# socket-a-1.net
KiCad netlist of a schematic drawn in EAGLE
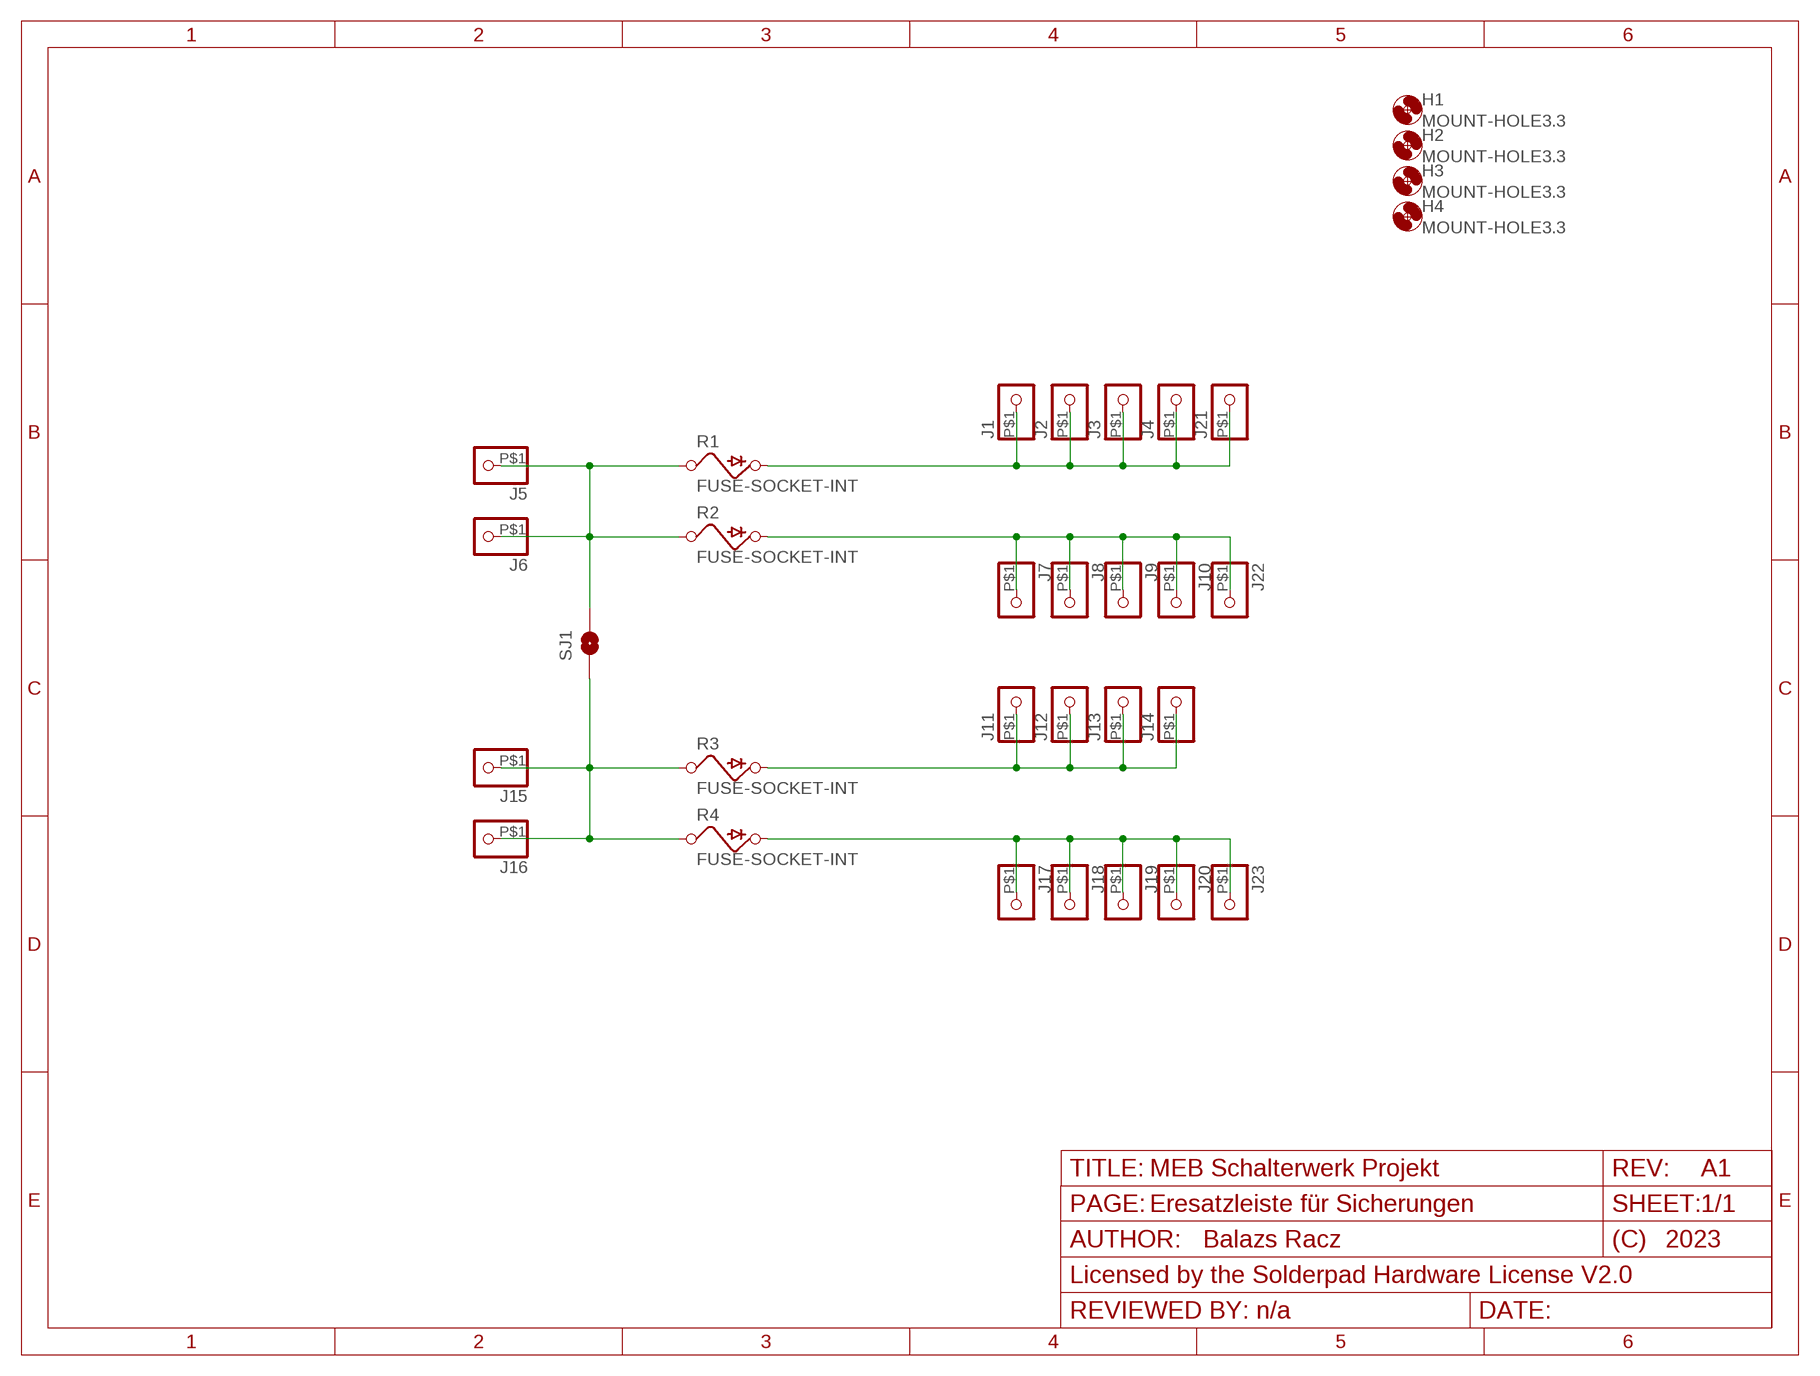
[diagram p0: schematic, sheet 1]

(export (version "E")
  (design (tool "Eeschema 10.0.6"))
  (components
    (comp (ref "H1")
      (value "MOUNT-HOLE3.3")
      (footprint "eagle-import:3,3")
      (libsource (lib "eagle-import") (part "MOUNT-HOLE3.3"))
    )
    (comp (ref "H2")
      (value "MOUNT-HOLE3.3")
      (footprint "eagle-import:3,3")
      (libsource (lib "eagle-import") (part "MOUNT-HOLE3.3"))
    )
    (comp (ref "H3")
      (value "MOUNT-HOLE3.3")
      (footprint "eagle-import:3,3")
      (libsource (lib "eagle-import") (part "MOUNT-HOLE3.3"))
    )
    (comp (ref "H4")
      (value "MOUNT-HOLE3.3")
      (footprint "eagle-import:3,3")
      (libsource (lib "eagle-import") (part "MOUNT-HOLE3.3"))
    )
    (comp (ref "J1")
      (value "LARGE-SOLDERPAD")
      (footprint "eagle-import:LARGE-SOLDERPAD")
      (libsource (lib "eagle-import") (part "LARGE-SOLDERPAD"))
    )
    (comp (ref "J2")
      (value "LARGE-SOLDERPAD")
      (footprint "eagle-import:LARGE-SOLDERPAD")
      (libsource (lib "eagle-import") (part "LARGE-SOLDERPAD"))
    )
    (comp (ref "J3")
      (value "LARGE-SOLDERPAD")
      (footprint "eagle-import:LARGE-SOLDERPAD")
      (libsource (lib "eagle-import") (part "LARGE-SOLDERPAD"))
    )
    (comp (ref "J4")
      (value "LARGE-SOLDERPAD")
      (footprint "eagle-import:LARGE-SOLDERPAD")
      (libsource (lib "eagle-import") (part "LARGE-SOLDERPAD"))
    )
    (comp (ref "J5")
      (value "LARGE-SOLDERPAD")
      (footprint "eagle-import:LARGE-SOLDERPAD")
      (libsource (lib "eagle-import") (part "LARGE-SOLDERPAD"))
    )
    (comp (ref "J6")
      (value "LARGE-SOLDERPAD")
      (footprint "eagle-import:LARGE-SOLDERPAD")
      (libsource (lib "eagle-import") (part "LARGE-SOLDERPAD"))
    )
    (comp (ref "J7")
      (value "LARGE-SOLDERPAD")
      (footprint "eagle-import:LARGE-SOLDERPAD")
      (libsource (lib "eagle-import") (part "LARGE-SOLDERPAD"))
    )
    (comp (ref "J8")
      (value "LARGE-SOLDERPAD")
      (footprint "eagle-import:LARGE-SOLDERPAD")
      (libsource (lib "eagle-import") (part "LARGE-SOLDERPAD"))
    )
    (comp (ref "J9")
      (value "LARGE-SOLDERPAD")
      (footprint "eagle-import:LARGE-SOLDERPAD")
      (libsource (lib "eagle-import") (part "LARGE-SOLDERPAD"))
    )
    (comp (ref "J10")
      (value "LARGE-SOLDERPAD")
      (footprint "eagle-import:LARGE-SOLDERPAD")
      (libsource (lib "eagle-import") (part "LARGE-SOLDERPAD"))
    )
    (comp (ref "J11")
      (value "LARGE-SOLDERPAD")
      (footprint "eagle-import:LARGE-SOLDERPAD")
      (libsource (lib "eagle-import") (part "LARGE-SOLDERPAD"))
    )
    (comp (ref "J12")
      (value "LARGE-SOLDERPAD")
      (footprint "eagle-import:LARGE-SOLDERPAD")
      (libsource (lib "eagle-import") (part "LARGE-SOLDERPAD"))
    )
    (comp (ref "J13")
      (value "LARGE-SOLDERPAD")
      (footprint "eagle-import:LARGE-SOLDERPAD")
      (libsource (lib "eagle-import") (part "LARGE-SOLDERPAD"))
    )
    (comp (ref "J14")
      (value "LARGE-SOLDERPAD")
      (footprint "eagle-import:LARGE-SOLDERPAD")
      (libsource (lib "eagle-import") (part "LARGE-SOLDERPAD"))
    )
    (comp (ref "J15")
      (value "LARGE-SOLDERPAD")
      (footprint "eagle-import:LARGE-SOLDERPAD")
      (libsource (lib "eagle-import") (part "LARGE-SOLDERPAD"))
    )
    (comp (ref "J16")
      (value "LARGE-SOLDERPAD")
      (footprint "eagle-import:LARGE-SOLDERPAD")
      (libsource (lib "eagle-import") (part "LARGE-SOLDERPAD"))
    )
    (comp (ref "J17")
      (value "LARGE-SOLDERPAD")
      (footprint "eagle-import:LARGE-SOLDERPAD")
      (libsource (lib "eagle-import") (part "LARGE-SOLDERPAD"))
    )
    (comp (ref "J18")
      (value "LARGE-SOLDERPAD")
      (footprint "eagle-import:LARGE-SOLDERPAD")
      (libsource (lib "eagle-import") (part "LARGE-SOLDERPAD"))
    )
    (comp (ref "J19")
      (value "LARGE-SOLDERPAD")
      (footprint "eagle-import:LARGE-SOLDERPAD")
      (libsource (lib "eagle-import") (part "LARGE-SOLDERPAD"))
    )
    (comp (ref "J20")
      (value "LARGE-SOLDERPAD")
      (footprint "eagle-import:LARGE-SOLDERPAD")
      (libsource (lib "eagle-import") (part "LARGE-SOLDERPAD"))
    )
    (comp (ref "J21")
      (value "LARGE-SOLDERPAD")
      (footprint "eagle-import:LARGE-SOLDERPAD")
      (libsource (lib "eagle-import") (part "LARGE-SOLDERPAD"))
    )
    (comp (ref "J22")
      (value "LARGE-SOLDERPAD")
      (footprint "eagle-import:LARGE-SOLDERPAD")
      (libsource (lib "eagle-import") (part "LARGE-SOLDERPAD"))
    )
    (comp (ref "J23")
      (value "LARGE-SOLDERPAD")
      (footprint "eagle-import:LARGE-SOLDERPAD")
      (libsource (lib "eagle-import") (part "LARGE-SOLDERPAD"))
    )
    (comp (ref "R1")
      (value "FUSE-SOCKET-INT")
      (footprint "eagle-import:FUSE-SOCKET-INT")
      (libsource (lib "eagle-import") (part "FUSE-SOCKET-INT"))
    )
    (comp (ref "R2")
      (value "FUSE-SOCKET-INT")
      (footprint "eagle-import:FUSE-SOCKET-INT")
      (libsource (lib "eagle-import") (part "FUSE-SOCKET-INT"))
    )
    (comp (ref "R3")
      (value "FUSE-SOCKET-INT")
      (footprint "eagle-import:FUSE-SOCKET-INT")
      (libsource (lib "eagle-import") (part "FUSE-SOCKET-INT"))
    )
    (comp (ref "R4")
      (value "FUSE-SOCKET-INT")
      (footprint "eagle-import:FUSE-SOCKET-INT")
      (libsource (lib "eagle-import") (part "FUSE-SOCKET-INT"))
    )
    (comp (ref "SJ1")
      (value "SJRND2")
      (footprint "eagle-import:SJ_RND2")
      (libsource (lib "eagle-import") (part "SJRND2"))
    )
  )
  (nets
    (net (code "1") (name "Net-(J1-1)") (class "Default")
      (node (ref "J1") (pin "P$1") (pinfunction "1_P$1") (pintype "passive"))
      (node (ref "J2") (pin "P$1") (pinfunction "1_P$1") (pintype "passive"))
      (node (ref "J21") (pin "P$1") (pinfunction "1_P$1") (pintype "passive"))
      (node (ref "J3") (pin "P$1") (pinfunction "1_P$1") (pintype "passive"))
      (node (ref "J4") (pin "P$1") (pinfunction "1_P$1") (pintype "passive"))
      (node (ref "R1") (pin "POUT") (pinfunction "POUT_POUT") (pintype "passive"))
    )
    (net (code "2") (name "Net-(J5-1)") (class "Default")
      (node (ref "J5") (pin "P$1") (pinfunction "1_P$1") (pintype "passive"))
      (node (ref "J6") (pin "P$1") (pinfunction "1_P$1") (pintype "passive"))
      (node (ref "R1") (pin "PIN1") (pinfunction "PIN_PIN1") (pintype "passive"))
      (node (ref "R1") (pin "PIN2") (pinfunction "PIN_PIN2") (pintype "passive"))
      (node (ref "R2") (pin "PIN1") (pinfunction "PIN_PIN1") (pintype "passive"))
      (node (ref "R2") (pin "PIN2") (pinfunction "PIN_PIN2") (pintype "passive"))
      (node (ref "SJ1") (pin "P$2") (pinfunction "2_P$2") (pintype "passive"))
    )
    (net (code "3") (name "Net-(J10-1)") (class "Default")
      (node (ref "J10") (pin "P$1") (pinfunction "1_P$1") (pintype "passive"))
      (node (ref "J22") (pin "P$1") (pinfunction "1_P$1") (pintype "passive"))
      (node (ref "J7") (pin "P$1") (pinfunction "1_P$1") (pintype "passive"))
      (node (ref "J8") (pin "P$1") (pinfunction "1_P$1") (pintype "passive"))
      (node (ref "J9") (pin "P$1") (pinfunction "1_P$1") (pintype "passive"))
      (node (ref "R2") (pin "POUT") (pinfunction "POUT_POUT") (pintype "passive"))
    )
    (net (code "4") (name "Net-(J11-1)") (class "Default")
      (node (ref "J11") (pin "P$1") (pinfunction "1_P$1") (pintype "passive"))
      (node (ref "J12") (pin "P$1") (pinfunction "1_P$1") (pintype "passive"))
      (node (ref "J13") (pin "P$1") (pinfunction "1_P$1") (pintype "passive"))
      (node (ref "J14") (pin "P$1") (pinfunction "1_P$1") (pintype "passive"))
      (node (ref "R3") (pin "POUT") (pinfunction "POUT_POUT") (pintype "passive"))
    )
    (net (code "5") (name "Net-(J15-1)") (class "Default")
      (node (ref "J15") (pin "P$1") (pinfunction "1_P$1") (pintype "passive"))
      (node (ref "J16") (pin "P$1") (pinfunction "1_P$1") (pintype "passive"))
      (node (ref "R3") (pin "PIN1") (pinfunction "PIN_PIN1") (pintype "passive"))
      (node (ref "R3") (pin "PIN2") (pinfunction "PIN_PIN2") (pintype "passive"))
      (node (ref "R4") (pin "PIN1") (pinfunction "PIN_PIN1") (pintype "passive"))
      (node (ref "R4") (pin "PIN2") (pinfunction "PIN_PIN2") (pintype "passive"))
      (node (ref "SJ1") (pin "P$1") (pinfunction "1_P$1") (pintype "passive"))
    )
    (net (code "6") (name "Net-(J17-1)") (class "Default")
      (node (ref "J17") (pin "P$1") (pinfunction "1_P$1") (pintype "passive"))
      (node (ref "J18") (pin "P$1") (pinfunction "1_P$1") (pintype "passive"))
      (node (ref "J19") (pin "P$1") (pinfunction "1_P$1") (pintype "passive"))
      (node (ref "J20") (pin "P$1") (pinfunction "1_P$1") (pintype "passive"))
      (node (ref "J23") (pin "P$1") (pinfunction "1_P$1") (pintype "passive"))
      (node (ref "R4") (pin "POUT") (pinfunction "POUT_POUT") (pintype "passive"))
    )
  )
)
